# Ethernet_Con.net
KiCad netlist of a schematic drawn in Altium Designer
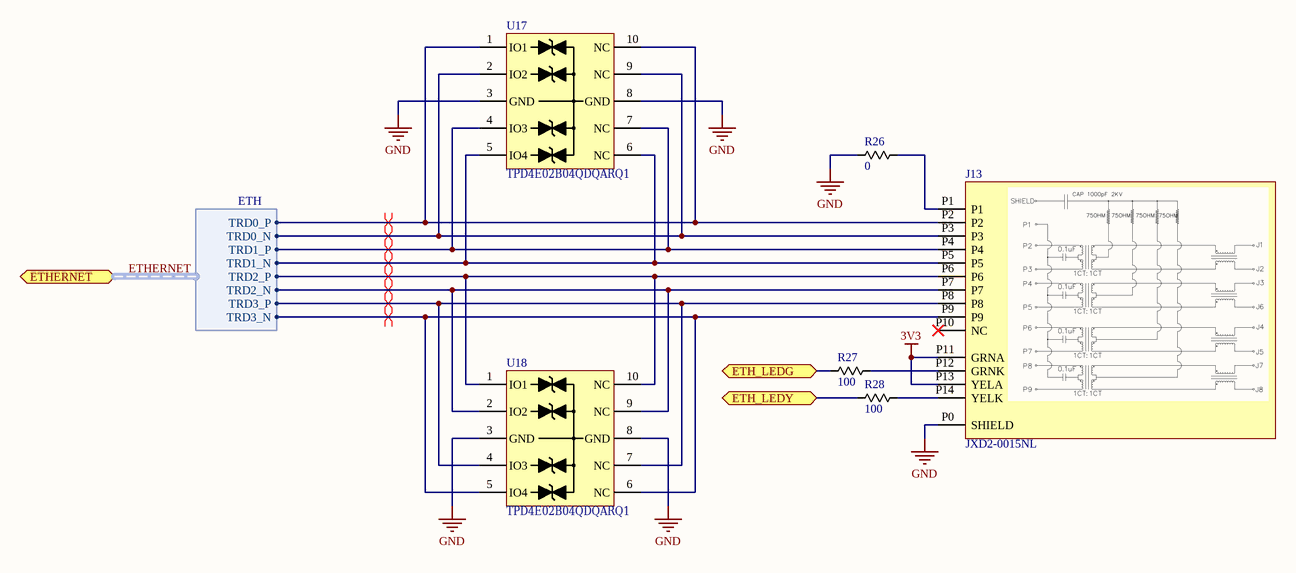
[diagram p0: Ethernet Con.SchDoc]

(export (version "E")
  (design (tool "Eeschema 10.0.6"))
  (components
    (comp (ref "J13")
      (value "JXD2-0015NL")
      (footprint "PULSE_JXD2-0015NL")
      (description "RJ45 Modular Mag-jack, 8P8C, 1000 Base-T, Vertical")
      (fields
        (field (name "PART NUMBER") "CONN-00115")
        (field (name "MANUFACTURER") "Pulse Electronics Network")
      )
      (libsource (lib "Connectors$") (part "CONN-00115"))
    )
    (comp (ref "R26")
      (value "0")
      (footprint "chip_0805")
      (description "RES SMD 0 OHM 1/8W 0805 Thick Film")
      (fields (field (name "PART NUMBER") "RES-00720") (field (name "TOLERANCE") "Jumper"))
      (libsource (lib "Resistors$") (part "RES-00720"))
    )
    (comp (ref "R27")
      (value "100")
      (footprint "chip_0603")
      (description "RES SMD 100 OHM 1% 1/4W 0603")
      (fields (field (name "PART NUMBER") "RES-00178") (field (name "TOLERANCE") "1%"))
      (libsource (lib "Resistors$") (part "RES-00178"))
    )
    (comp (ref "R28")
      (value "100")
      (footprint "chip_0603")
      (description "RES SMD 100 OHM 1% 1/4W 0603")
      (fields (field (name "PART NUMBER") "RES-00178") (field (name "TOLERANCE") "1%"))
      (libsource (lib "Resistors$") (part "RES-00178"))
    )
    (comp (ref "U17")
      (value "TPD4E02B04QDQARQ1‎")
      (footprint "USON-10")
      (description "TVS, 4-Ch, ESD Protec, 3.6V 8.8V 10-USON")
      (fields (field (name "PART NUMBER") "DIO-00068") (field (name "MANUFACTURER") "TI"))
      (libsource (lib "Diodes$") (part "DIO-00068"))
    )
    (comp (ref "U18")
      (value "TPD4E02B04QDQARQ1‎")
      (footprint "USON-10")
      (description "TVS, 4-Ch, ESD Protec, 3.6V 8.8V 10-USON")
      (fields (field (name "PART NUMBER") "DIO-00068") (field (name "MANUFACTURER") "TI"))
      (libsource (lib "Diodes$") (part "DIO-00068"))
    )
  )
  (nets
    (net (code "3") (name "/ETH_LEDG") (class "Default")
      (node (ref "R27") (pin "1") (pinfunction "1_1") (pintype "passive"))
    )
    (net (code "4") (name "/ETH_LEDY") (class "Default")
      (node (ref "R28") (pin "1") (pinfunction "1_1") (pintype "passive"))
    )
    (net (code "5") (name "3V3") (class "Default")
      (node (ref "J13") (pin "P11") (pinfunction "GRNA_P11") (pintype "passive"))
      (node (ref "J13") (pin "P13") (pinfunction "YELA_P13") (pintype "passive"))
    )
    (net (code "6") (name "GND") (class "Default")
      (node (ref "J13") (pin "P0") (pinfunction "SHIELD_P0") (pintype "passive"))
      (node (ref "R26") (pin "1") (pinfunction "1_1") (pintype "passive"))
      (node (ref "U17") (pin "3") (pinfunction "GND_3") (pintype "passive"))
      (node (ref "U17") (pin "8") (pinfunction "GND_8") (pintype "passive"))
      (node (ref "U18") (pin "3") (pinfunction "GND_3") (pintype "passive"))
      (node (ref "U18") (pin "8") (pinfunction "GND_8") (pintype "passive"))
    )
    (net (code "7") (name "Net-(J13-GRNK)") (class "Default")
      (node (ref "J13") (pin "P12") (pinfunction "GRNK_P12") (pintype "passive"))
      (node (ref "R27") (pin "2") (pinfunction "2_2") (pintype "passive"))
    )
    (net (code "8") (name "Net-(J13-PadP1)") (class "Default")
      (node (ref "J13") (pin "P1") (pinfunction "P1_P1") (pintype "passive"))
      (node (ref "R26") (pin "2") (pinfunction "2_2") (pintype "passive"))
    )
    (net (code "9") (name "Net-(J13-YELK)") (class "Default")
      (node (ref "J13") (pin "P14") (pinfunction "YELK_P14") (pintype "passive"))
      (node (ref "R28") (pin "2") (pinfunction "2_2") (pintype "passive"))
    )
    (net (code "10") (name "Net-(U17-IO1)") (class "Default")
      (node (ref "J13") (pin "P2") (pinfunction "P2_P2") (pintype "passive"))
      (node (ref "U17") (pin "1") (pinfunction "IO1_1") (pintype "passive"))
      (node (ref "U17") (pin "10") (pinfunction "NC_10") (pintype "passive"))
    )
    (net (code "11") (name "Net-(U17-IO2)") (class "Default")
      (node (ref "J13") (pin "P3") (pinfunction "P3_P3") (pintype "passive"))
      (node (ref "U17") (pin "2") (pinfunction "IO2_2") (pintype "passive"))
      (node (ref "U17") (pin "9") (pinfunction "NC_9") (pintype "passive"))
    )
    (net (code "12") (name "Net-(U17-IO3)") (class "Default")
      (node (ref "J13") (pin "P4") (pinfunction "P4_P4") (pintype "passive"))
      (node (ref "U17") (pin "4") (pinfunction "IO3_4") (pintype "passive"))
      (node (ref "U17") (pin "7") (pinfunction "NC_7") (pintype "passive"))
    )
    (net (code "13") (name "Net-(U17-IO4)") (class "Default")
      (node (ref "J13") (pin "P5") (pinfunction "P5_P5") (pintype "passive"))
      (node (ref "U17") (pin "5") (pinfunction "IO4_5") (pintype "passive"))
      (node (ref "U17") (pin "6") (pinfunction "NC_6") (pintype "passive"))
    )
    (net (code "14") (name "Net-(U18-IO1)") (class "Default")
      (node (ref "J13") (pin "P6") (pinfunction "P6_P6") (pintype "passive"))
      (node (ref "U18") (pin "1") (pinfunction "IO1_1") (pintype "passive"))
      (node (ref "U18") (pin "10") (pinfunction "NC_10") (pintype "passive"))
    )
    (net (code "15") (name "Net-(U18-IO2)") (class "Default")
      (node (ref "J13") (pin "P7") (pinfunction "P7_P7") (pintype "passive"))
      (node (ref "U18") (pin "2") (pinfunction "IO2_2") (pintype "passive"))
      (node (ref "U18") (pin "9") (pinfunction "NC_9") (pintype "passive"))
    )
    (net (code "16") (name "Net-(U18-IO3)") (class "Default")
      (node (ref "J13") (pin "P8") (pinfunction "P8_P8") (pintype "passive"))
      (node (ref "U18") (pin "4") (pinfunction "IO3_4") (pintype "passive"))
      (node (ref "U18") (pin "7") (pinfunction "NC_7") (pintype "passive"))
    )
    (net (code "17") (name "Net-(U18-IO4)") (class "Default")
      (node (ref "J13") (pin "P9") (pinfunction "P9_P9") (pintype "passive"))
      (node (ref "U18") (pin "5") (pinfunction "IO4_5") (pintype "passive"))
      (node (ref "U18") (pin "6") (pinfunction "NC_6") (pintype "passive"))
    )
    (net (code "18") (name "unconnected-(J13-NC-PadP10)") (class "Default")
      (node (ref "J13") (pin "P10") (pinfunction "NC_P10") (pintype "passive+no_connect"))
    )
  )
)
